# E.net
KiCad netlist of a schematic drawn in EAGLE
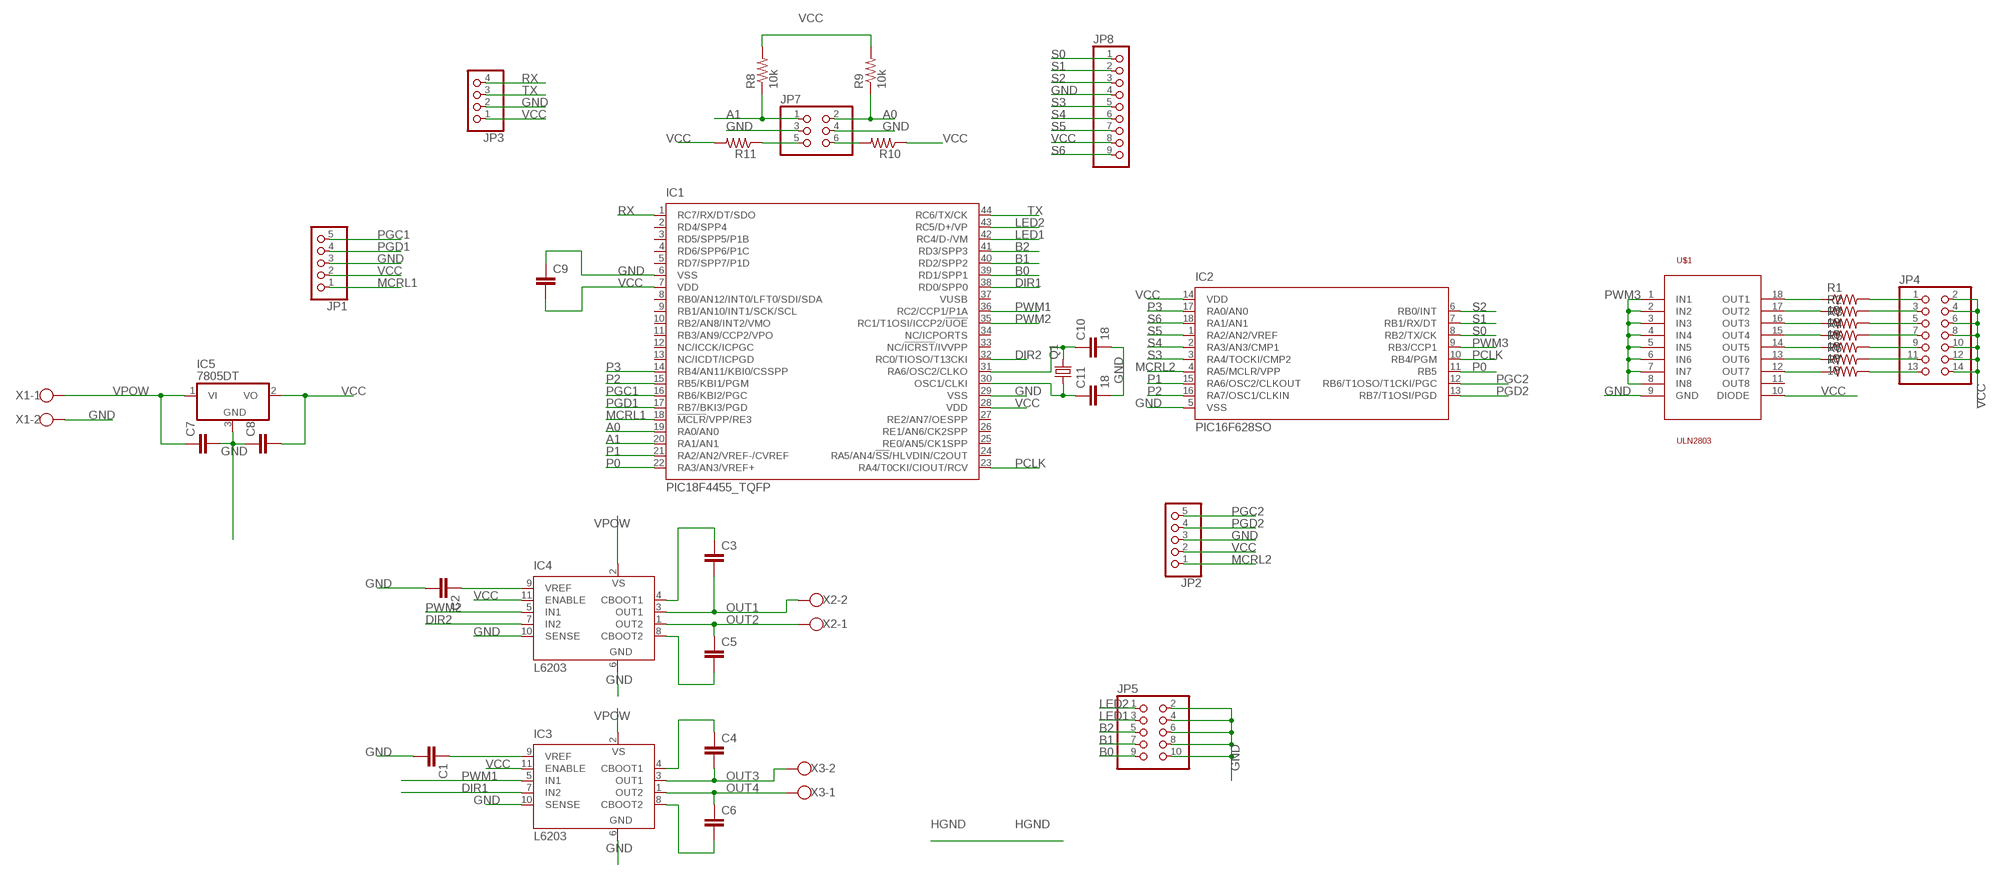
[diagram p0: schematic, sheet 1]

(export (version "E")
  (design (tool "Eeschema 10.0.6"))
  (components
    (comp (ref "C1")
      (value "C2,5-3")
      (footprint "eagle-import:C2.5-3")
      (libsource (lib "eagle-import") (part "C2,5-3"))
    )
    (comp (ref "C2")
      (value "C2,5-3")
      (footprint "eagle-import:C2.5-3")
      (libsource (lib "eagle-import") (part "C2,5-3"))
    )
    (comp (ref "C3")
      (value "C2,5-3")
      (footprint "eagle-import:C2.5-3")
      (libsource (lib "eagle-import") (part "C2,5-3"))
    )
    (comp (ref "C4")
      (value "C2,5-3")
      (footprint "eagle-import:C2.5-3")
      (libsource (lib "eagle-import") (part "C2,5-3"))
    )
    (comp (ref "C5")
      (value "C2,5-3")
      (footprint "eagle-import:C2.5-3")
      (libsource (lib "eagle-import") (part "C2,5-3"))
    )
    (comp (ref "C6")
      (value "C2,5-3")
      (footprint "eagle-import:C2.5-3")
      (libsource (lib "eagle-import") (part "C2,5-3"))
    )
    (comp (ref "C7")
      (value "C2,5-3")
      (footprint "eagle-import:C2.5-3")
      (libsource (lib "eagle-import") (part "C2,5-3"))
    )
    (comp (ref "C8")
      (value "C2,5-3")
      (footprint "eagle-import:C2.5-3")
      (libsource (lib "eagle-import") (part "C2,5-3"))
    )
    (comp (ref "C9")
      (value "C2,5-3")
      (footprint "eagle-import:C2.5-3")
      (libsource (lib "eagle-import") (part "C2,5-3"))
    )
    (comp (ref "C10")
      (value "18")
      (footprint "eagle-import:C2.5-3")
      (libsource (lib "eagle-import") (part "C2,5-3"))
    )
    (comp (ref "C11")
      (value "18")
      (footprint "eagle-import:C2.5-3")
      (libsource (lib "eagle-import") (part "C2,5-3"))
    )
    (comp (ref "IC1")
      (value "PIC18F4455_TQFP")
      (footprint "eagle-import:TQFP44")
      (fields (field (name "MF") "MICROCHIP") (field (name "MPN") "PIC18F4455-I/PT"))
      (libsource (lib "eagle-import") (part "PIC18F4_TQFP455"))
    )
    (comp (ref "IC2")
      (value "PIC16F628SO")
      (footprint "eagle-import:SO-18W")
      (fields (field (name "MF") "MICROCHIP") (field (name "MPN") "PIC16F628-20I/SO"))
      (libsource (lib "eagle-import") (part "PIC16F62SO8"))
    )
    (comp (ref "IC3")
      (value "L6203")
      (footprint "eagle-import:MULTIWATT-11")
      (libsource (lib "eagle-import") (part "L6203"))
    )
    (comp (ref "IC4")
      (value "L6203")
      (footprint "eagle-import:MULTIWATT-11")
      (libsource (lib "eagle-import") (part "L6203"))
    )
    (comp (ref "IC5")
      (value "7805DT")
      (footprint "eagle-import:TO252")
      (libsource (lib "eagle-import") (part "78DT05"))
    )
    (comp (ref "JP1")
      (value "PINHD-1X5")
      (footprint "eagle-import:1X05")
      (libsource (lib "eagle-import") (part "PINHD-1X5"))
    )
    (comp (ref "JP2")
      (value "PINHD-1X5")
      (footprint "eagle-import:1X05")
      (libsource (lib "eagle-import") (part "PINHD-1X5"))
    )
    (comp (ref "JP3")
      (value "PINHD-1X4")
      (footprint "eagle-import:1X04")
      (libsource (lib "eagle-import") (part "PINHD-1X4"))
    )
    (comp (ref "JP4")
      (value "PINHD-2X7")
      (footprint "eagle-import:2X07")
      (libsource (lib "eagle-import") (part "PINHD-2X7"))
    )
    (comp (ref "JP5")
      (value "PINHD-2X5")
      (footprint "eagle-import:2X05")
      (libsource (lib "eagle-import") (part "PINHD-2X5"))
    )
    (comp (ref "JP7")
      (value "PINHD-2X3")
      (footprint "eagle-import:2X03")
      (libsource (lib "eagle-import") (part "PINHD-2X3"))
    )
    (comp (ref "JP8")
      (value "PINHD-1X9")
      (footprint "eagle-import:1X09")
      (libsource (lib "eagle-import") (part "PINHD-1X9"))
    )
    (comp (ref "Q1")
      (value "CRYSTALHC49S")
      (footprint "eagle-import:HC49_S")
      (libsource (lib "eagle-import") (part "CRYSTALHC49S"))
    )
    (comp (ref "R1")
      (value "18")
      (footprint "eagle-import:M1206")
      (libsource (lib "eagle-import") (part "R-US_M1206"))
    )
    (comp (ref "R2")
      (value "18")
      (footprint "eagle-import:M1206")
      (libsource (lib "eagle-import") (part "R-US_M1206"))
    )
    (comp (ref "R3")
      (value "18")
      (footprint "eagle-import:M1206")
      (libsource (lib "eagle-import") (part "R-US_M1206"))
    )
    (comp (ref "R4")
      (value "18")
      (footprint "eagle-import:M1206")
      (libsource (lib "eagle-import") (part "R-US_M1206"))
    )
    (comp (ref "R5")
      (value "18")
      (footprint "eagle-import:M1206")
      (libsource (lib "eagle-import") (part "R-US_M1206"))
    )
    (comp (ref "R6")
      (value "18")
      (footprint "eagle-import:M1206")
      (libsource (lib "eagle-import") (part "R-US_M1206"))
    )
    (comp (ref "R7")
      (value "R-US_M1206")
      (footprint "eagle-import:M1206")
      (libsource (lib "eagle-import") (part "R-US_M1206"))
    )
    (comp (ref "R8")
      (value "10k")
      (footprint "eagle-import:M1206")
      (libsource (lib "eagle-import") (part "R-US_M1206"))
    )
    (comp (ref "R9")
      (value "10k")
      (footprint "eagle-import:M1206")
      (libsource (lib "eagle-import") (part "R-US_M1206"))
    )
    (comp (ref "R10")
      (value "R-US_M1206")
      (footprint "eagle-import:M1206")
      (libsource (lib "eagle-import") (part "R-US_M1206"))
    )
    (comp (ref "R11")
      (value "R-US_M1206")
      (footprint "eagle-import:M1206")
      (libsource (lib "eagle-import") (part "R-US_M1206"))
    )
    (comp (ref "U$1")
      (value "ULN2803")
      (footprint "eagle-import:SO18L")
      (libsource (lib "eagle-import") (part "ULN2803"))
    )
    (comp (ref "X1")
      (value "W237-102")
      (footprint "eagle-import:W237-102")
      (fields (field (name "MPN") "237-102"))
      (libsource (lib "eagle-import") (part "W237-102"))
    )
    (comp (ref "X2")
      (value "W237-102")
      (footprint "eagle-import:W237-102")
      (fields (field (name "MPN") "237-102"))
      (libsource (lib "eagle-import") (part "W237-102"))
    )
    (comp (ref "X3")
      (value "W237-102")
      (footprint "eagle-import:W237-102")
      (fields (field (name "MPN") "237-102"))
      (libsource (lib "eagle-import") (part "W237-102"))
    )
  )
  (nets
    (net (code "1") (name "/A0") (class "Default")
      (node (ref "IC1") (pin "19") (pinfunction "RA0/AN0_19") (pintype "bidirectional"))
      (node (ref "JP7") (pin "2") (pinfunction "2_2") (pintype "passive"))
      (node (ref "R9") (pin "1") (pinfunction "1_1") (pintype "passive"))
    )
    (net (code "2") (name "/A1") (class "Default")
      (node (ref "IC1") (pin "20") (pinfunction "RA1/AN1_20") (pintype "bidirectional"))
      (node (ref "JP7") (pin "1") (pinfunction "1_1") (pintype "passive"))
      (node (ref "R8") (pin "1") (pinfunction "1_1") (pintype "passive"))
    )
    (net (code "3") (name "/B0") (class "Default")
      (node (ref "IC1") (pin "39") (pinfunction "RD1/SPP1_39") (pintype "bidirectional"))
      (node (ref "JP5") (pin "9") (pinfunction "9_9") (pintype "passive"))
    )
    (net (code "4") (name "/B1") (class "Default")
      (node (ref "IC1") (pin "40") (pinfunction "RD2/SPP2_40") (pintype "bidirectional"))
      (node (ref "JP5") (pin "7") (pinfunction "7_7") (pintype "passive"))
    )
    (net (code "5") (name "/B2") (class "Default")
      (node (ref "IC1") (pin "41") (pinfunction "RD3/SPP3_41") (pintype "bidirectional"))
      (node (ref "JP5") (pin "5") (pinfunction "5_5") (pintype "passive"))
    )
    (net (code "6") (name "/DIR1") (class "Default")
      (node (ref "IC1") (pin "38") (pinfunction "RD0/SPP0_38") (pintype "bidirectional"))
      (node (ref "IC3") (pin "7") (pinfunction "IN2_7") (pintype "input"))
    )
    (net (code "7") (name "/DIR2") (class "Default")
      (node (ref "IC1") (pin "32") (pinfunction "RC0/TIOSO/T13CKI_32") (pintype "bidirectional"))
      (node (ref "IC4") (pin "7") (pinfunction "IN2_7") (pintype "input"))
    )
    (net (code "8") (name "/GND") (class "Default")
      (node (ref "C1") (pin "2") (pinfunction "2_2") (pintype "passive"))
      (node (ref "C10") (pin "2") (pinfunction "2_2") (pintype "passive"))
      (node (ref "C11") (pin "2") (pinfunction "2_2") (pintype "passive"))
      (node (ref "C2") (pin "2") (pinfunction "2_2") (pintype "passive"))
      (node (ref "C7") (pin "2") (pinfunction "2_2") (pintype "passive"))
      (node (ref "C8") (pin "1") (pinfunction "1_1") (pintype "passive"))
      (node (ref "C9") (pin "1") (pinfunction "1_1") (pintype "passive"))
      (node (ref "IC1") (pin "29") (pinfunction "VSS_29") (pintype "power_in"))
      (node (ref "IC1") (pin "6") (pinfunction "VSS_6") (pintype "power_in"))
      (node (ref "IC2") (pin "5") (pinfunction "VSS_5") (pintype "power_in"))
      (node (ref "IC3") (pin "10") (pinfunction "SENSE_10") (pintype "input"))
      (node (ref "IC3") (pin "6") (pinfunction "GND_6") (pintype "power_in"))
      (node (ref "IC4") (pin "10") (pinfunction "SENSE_10") (pintype "input"))
      (node (ref "IC4") (pin "6") (pinfunction "GND_6") (pintype "power_in"))
      (node (ref "IC5") (pin "3") (pinfunction "GND_3") (pintype "passive"))
      (node (ref "JP1") (pin "3") (pinfunction "3_3") (pintype "passive"))
      (node (ref "JP2") (pin "3") (pinfunction "3_3") (pintype "passive"))
      (node (ref "JP3") (pin "2") (pinfunction "2_2") (pintype "passive"))
      (node (ref "JP5") (pin "10") (pinfunction "10_10") (pintype "passive"))
      (node (ref "JP5") (pin "2") (pinfunction "2_2") (pintype "passive"))
      (node (ref "JP5") (pin "4") (pinfunction "4_4") (pintype "passive"))
      (node (ref "JP5") (pin "6") (pinfunction "6_6") (pintype "passive"))
      (node (ref "JP5") (pin "8") (pinfunction "8_8") (pintype "passive"))
      (node (ref "JP7") (pin "3") (pinfunction "3_3") (pintype "passive"))
      (node (ref "JP7") (pin "4") (pinfunction "4_4") (pintype "passive"))
      (node (ref "JP8") (pin "4") (pinfunction "4_4") (pintype "passive"))
      (node (ref "U$1") (pin "9") (pinfunction "GND_9") (pintype "power_in"))
      (node (ref "X1") (pin "2") (pinfunction "KL_2") (pintype "passive"))
    )
    (net (code "10") (name "/LED1") (class "Default")
      (node (ref "IC1") (pin "42") (pinfunction "RC4/D-/VM_42") (pintype "bidirectional"))
      (node (ref "JP5") (pin "3") (pinfunction "3_3") (pintype "passive"))
    )
    (net (code "11") (name "/LED2") (class "Default")
      (node (ref "IC1") (pin "43") (pinfunction "RC5/D+/VP_43") (pintype "bidirectional"))
      (node (ref "JP5") (pin "1") (pinfunction "1_1") (pintype "passive"))
    )
    (net (code "12") (name "/MCRL1") (class "Default")
      (node (ref "IC1") (pin "18") (pinfunction "~{MCLR}/VPP/RE3_18") (pintype "input"))
      (node (ref "JP1") (pin "1") (pinfunction "1_1") (pintype "passive"))
    )
    (net (code "13") (name "/MCRL2") (class "Default")
      (node (ref "IC2") (pin "4") (pinfunction "RA5/MCLR/VPP_4") (pintype "bidirectional"))
      (node (ref "JP2") (pin "1") (pinfunction "1_1") (pintype "passive"))
    )
    (net (code "14") (name "/OUT1") (class "Default")
      (node (ref "C3") (pin "2") (pinfunction "2_2") (pintype "passive"))
      (node (ref "IC4") (pin "3") (pinfunction "OUT1_3") (pintype "output"))
      (node (ref "X2") (pin "2") (pinfunction "KL_2") (pintype "passive"))
    )
    (net (code "15") (name "/OUT2") (class "Default")
      (node (ref "C5") (pin "1") (pinfunction "1_1") (pintype "passive"))
      (node (ref "IC4") (pin "1") (pinfunction "OUT2_1") (pintype "output"))
      (node (ref "X2") (pin "1") (pinfunction "KL_1") (pintype "passive"))
    )
    (net (code "16") (name "/OUT3") (class "Default")
      (node (ref "C4") (pin "2") (pinfunction "2_2") (pintype "passive"))
      (node (ref "IC3") (pin "3") (pinfunction "OUT1_3") (pintype "output"))
      (node (ref "X3") (pin "2") (pinfunction "KL_2") (pintype "passive"))
    )
    (net (code "17") (name "/OUT4") (class "Default")
      (node (ref "C6") (pin "1") (pinfunction "1_1") (pintype "passive"))
      (node (ref "IC3") (pin "1") (pinfunction "OUT2_1") (pintype "output"))
      (node (ref "X3") (pin "1") (pinfunction "KL_1") (pintype "passive"))
    )
    (net (code "18") (name "/P0") (class "Default")
      (node (ref "IC1") (pin "22") (pinfunction "RA3/AN3/VREF+_22") (pintype "bidirectional"))
      (node (ref "IC2") (pin "11") (pinfunction "RB5_11") (pintype "bidirectional"))
    )
    (net (code "19") (name "/P1") (class "Default")
      (node (ref "IC1") (pin "21") (pinfunction "RA2/AN2/VREF-/CVREF_21") (pintype "bidirectional"))
      (node (ref "IC2") (pin "15") (pinfunction "RA6/OSC2/CLKOUT_15") (pintype "bidirectional"))
    )
    (net (code "20") (name "/P2") (class "Default")
      (node (ref "IC1") (pin "15") (pinfunction "RB5/KBI1/PGM_15") (pintype "bidirectional"))
      (node (ref "IC2") (pin "16") (pinfunction "RA7/OSC1/CLKIN_16") (pintype "bidirectional"))
    )
    (net (code "21") (name "/P3") (class "Default")
      (node (ref "IC1") (pin "14") (pinfunction "RB4/AN11/KBI0/CSSPP_14") (pintype "bidirectional"))
      (node (ref "IC2") (pin "17") (pinfunction "RA0/AN0_17") (pintype "bidirectional"))
    )
    (net (code "22") (name "/PCLK") (class "Default")
      (node (ref "IC1") (pin "23") (pinfunction "RA4/T0CKI/CIOUT/RCV_23") (pintype "bidirectional"))
      (node (ref "IC2") (pin "10") (pinfunction "RB4/PGM_10") (pintype "bidirectional"))
    )
    (net (code "23") (name "/PGC1") (class "Default")
      (node (ref "IC1") (pin "16") (pinfunction "RB6/KBI2/PGC_16") (pintype "bidirectional"))
      (node (ref "JP1") (pin "5") (pinfunction "5_5") (pintype "passive"))
    )
    (net (code "24") (name "/PGC2") (class "Default")
      (node (ref "IC2") (pin "12") (pinfunction "RB6/T1OSO/T1CKI/PGC_12") (pintype "bidirectional"))
      (node (ref "JP2") (pin "5") (pinfunction "5_5") (pintype "passive"))
    )
    (net (code "25") (name "/PGD1") (class "Default")
      (node (ref "IC1") (pin "17") (pinfunction "RB7/BKI3/PGD_17") (pintype "bidirectional"))
      (node (ref "JP1") (pin "4") (pinfunction "4_4") (pintype "passive"))
    )
    (net (code "26") (name "/PGD2") (class "Default")
      (node (ref "IC2") (pin "13") (pinfunction "RB7/T1OSI/PGD_13") (pintype "bidirectional"))
      (node (ref "JP2") (pin "4") (pinfunction "4_4") (pintype "passive"))
    )
    (net (code "27") (name "/PWM1") (class "Default")
      (node (ref "IC1") (pin "36") (pinfunction "RC2/CCP1/P1A_36") (pintype "bidirectional"))
      (node (ref "IC3") (pin "5") (pinfunction "IN1_5") (pintype "input"))
    )
    (net (code "28") (name "/PWM2") (class "Default")
      (node (ref "IC1") (pin "35") (pinfunction "RC1/T1OSI/ICCP2/~{UOE}_35") (pintype "bidirectional"))
      (node (ref "IC4") (pin "5") (pinfunction "IN1_5") (pintype "input"))
    )
    (net (code "29") (name "/PWM3") (class "Default")
      (node (ref "IC2") (pin "9") (pinfunction "RB3/CCP1_9") (pintype "bidirectional"))
      (node (ref "U$1") (pin "1") (pinfunction "IN1_1") (pintype "input"))
      (node (ref "U$1") (pin "2") (pinfunction "IN2_2") (pintype "input"))
      (node (ref "U$1") (pin "3") (pinfunction "IN3_3") (pintype "input"))
      (node (ref "U$1") (pin "4") (pinfunction "IN4_4") (pintype "input"))
      (node (ref "U$1") (pin "5") (pinfunction "IN5_5") (pintype "input"))
      (node (ref "U$1") (pin "6") (pinfunction "IN6_6") (pintype "input"))
      (node (ref "U$1") (pin "7") (pinfunction "IN7_7") (pintype "input"))
      (node (ref "U$1") (pin "8") (pinfunction "IN8_8") (pintype "input"))
    )
    (net (code "30") (name "/RX") (class "Default")
      (node (ref "IC1") (pin "1") (pinfunction "RC7/RX/DT/SDO_1") (pintype "bidirectional"))
      (node (ref "JP3") (pin "4") (pinfunction "4_4") (pintype "passive"))
    )
    (net (code "31") (name "/S0") (class "Default")
      (node (ref "IC2") (pin "8") (pinfunction "RB2/TX/CK_8") (pintype "bidirectional"))
      (node (ref "JP8") (pin "1") (pinfunction "1_1") (pintype "passive"))
    )
    (net (code "32") (name "/S1") (class "Default")
      (node (ref "IC2") (pin "7") (pinfunction "RB1/RX/DT_7") (pintype "bidirectional"))
      (node (ref "JP8") (pin "2") (pinfunction "2_2") (pintype "passive"))
    )
    (net (code "33") (name "/S2") (class "Default")
      (node (ref "IC2") (pin "6") (pinfunction "RB0/INT_6") (pintype "bidirectional"))
      (node (ref "JP8") (pin "3") (pinfunction "3_3") (pintype "passive"))
    )
    (net (code "34") (name "/S3") (class "Default")
      (node (ref "IC2") (pin "3") (pinfunction "RA4/TOCKI/CMP2_3") (pintype "bidirectional"))
      (node (ref "JP8") (pin "5") (pinfunction "5_5") (pintype "passive"))
    )
    (net (code "35") (name "/S4") (class "Default")
      (node (ref "IC2") (pin "2") (pinfunction "RA3/AN3/CMP1_2") (pintype "bidirectional"))
      (node (ref "JP8") (pin "6") (pinfunction "6_6") (pintype "passive"))
    )
    (net (code "36") (name "/S5") (class "Default")
      (node (ref "IC2") (pin "1") (pinfunction "RA2/AN2/VREF_1") (pintype "bidirectional"))
      (node (ref "JP8") (pin "7") (pinfunction "7_7") (pintype "passive"))
    )
    (net (code "37") (name "/S6") (class "Default")
      (node (ref "IC2") (pin "18") (pinfunction "RA1/AN1_18") (pintype "bidirectional"))
      (node (ref "JP8") (pin "9") (pinfunction "9_9") (pintype "passive"))
    )
    (net (code "38") (name "/TX") (class "Default")
      (node (ref "IC1") (pin "44") (pinfunction "RC6/TX/CK_44") (pintype "bidirectional"))
      (node (ref "JP3") (pin "3") (pinfunction "3_3") (pintype "passive"))
    )
    (net (code "39") (name "/VCC") (class "Default")
      (node (ref "C8") (pin "2") (pinfunction "2_2") (pintype "passive"))
      (node (ref "C9") (pin "2") (pinfunction "2_2") (pintype "passive"))
      (node (ref "IC1") (pin "28") (pinfunction "VDD_28") (pintype "power_in"))
      (node (ref "IC1") (pin "7") (pinfunction "VDD_7") (pintype "power_in"))
      (node (ref "IC2") (pin "14") (pinfunction "VDD_14") (pintype "power_in"))
      (node (ref "IC3") (pin "11") (pinfunction "ENABLE_11") (pintype "input"))
      (node (ref "IC4") (pin "11") (pinfunction "ENABLE_11") (pintype "input"))
      (node (ref "IC5") (pin "2") (pinfunction "VO_2") (pintype "passive"))
      (node (ref "JP1") (pin "2") (pinfunction "2_2") (pintype "passive"))
      (node (ref "JP2") (pin "2") (pinfunction "2_2") (pintype "passive"))
      (node (ref "JP3") (pin "1") (pinfunction "1_1") (pintype "passive"))
      (node (ref "JP4") (pin "10") (pinfunction "10_10") (pintype "passive"))
      (node (ref "JP4") (pin "12") (pinfunction "12_12") (pintype "passive"))
      (node (ref "JP4") (pin "14") (pinfunction "14_14") (pintype "passive"))
      (node (ref "JP4") (pin "2") (pinfunction "2_2") (pintype "passive"))
      (node (ref "JP4") (pin "4") (pinfunction "4_4") (pintype "passive"))
      (node (ref "JP4") (pin "6") (pinfunction "6_6") (pintype "passive"))
      (node (ref "JP4") (pin "8") (pinfunction "8_8") (pintype "passive"))
      (node (ref "JP8") (pin "8") (pinfunction "8_8") (pintype "passive"))
      (node (ref "R10") (pin "1") (pinfunction "1_1") (pintype "passive"))
      (node (ref "R11") (pin "2") (pinfunction "2_2") (pintype "passive"))
      (node (ref "R8") (pin "2") (pinfunction "2_2") (pintype "passive"))
      (node (ref "R9") (pin "2") (pinfunction "2_2") (pintype "passive"))
      (node (ref "U$1") (pin "10") (pinfunction "DIODE_10") (pintype "power_in"))
    )
    (net (code "40") (name "/VPOW") (class "Default")
      (node (ref "C7") (pin "1") (pinfunction "1_1") (pintype "passive"))
      (node (ref "IC3") (pin "2") (pinfunction "VS_2") (pintype "power_in"))
      (node (ref "IC4") (pin "2") (pinfunction "VS_2") (pintype "power_in"))
      (node (ref "IC5") (pin "1") (pinfunction "VI_1") (pintype "input"))
      (node (ref "X1") (pin "1") (pinfunction "KL_1") (pintype "passive"))
    )
    (net (code "41") (name "Net-(IC1-OSC1{slash}CLKI)") (class "Default")
      (node (ref "C11") (pin "1") (pinfunction "1_1") (pintype "passive"))
      (node (ref "IC1") (pin "30") (pinfunction "OSC1/CLKI_30") (pintype "input"))
      (node (ref "Q1") (pin "1") (pinfunction "1_1") (pintype "passive"))
    )
    (net (code "42") (name "Net-(IC1-RA6{slash}OSC2{slash}CLKO)") (class "Default")
      (node (ref "C10") (pin "1") (pinfunction "1_1") (pintype "passive"))
      (node (ref "IC1") (pin "31") (pinfunction "RA6/OSC2/CLKO_31") (pintype "output"))
      (node (ref "Q1") (pin "2") (pinfunction "2_2") (pintype "passive"))
    )
    (net (code "43") (name "Net-(IC3-CBOOT1)") (class "Default")
      (node (ref "C4") (pin "1") (pinfunction "1_1") (pintype "passive"))
      (node (ref "IC3") (pin "4") (pinfunction "CBOOT1_4") (pintype "input"))
    )
    (net (code "44") (name "Net-(IC3-CBOOT2)") (class "Default")
      (node (ref "C6") (pin "2") (pinfunction "2_2") (pintype "passive"))
      (node (ref "IC3") (pin "8") (pinfunction "CBOOT2_8") (pintype "input"))
    )
    (net (code "45") (name "Net-(IC3-VREF)") (class "Default")
      (node (ref "C1") (pin "1") (pinfunction "1_1") (pintype "passive"))
      (node (ref "IC3") (pin "9") (pinfunction "VREF_9") (pintype "input"))
    )
    (net (code "46") (name "Net-(IC4-CBOOT1)") (class "Default")
      (node (ref "C3") (pin "1") (pinfunction "1_1") (pintype "passive"))
      (node (ref "IC4") (pin "4") (pinfunction "CBOOT1_4") (pintype "input"))
    )
    (net (code "47") (name "Net-(IC4-CBOOT2)") (class "Default")
      (node (ref "C5") (pin "2") (pinfunction "2_2") (pintype "passive"))
      (node (ref "IC4") (pin "8") (pinfunction "CBOOT2_8") (pintype "input"))
    )
    (net (code "48") (name "Net-(IC4-VREF)") (class "Default")
      (node (ref "C2") (pin "1") (pinfunction "1_1") (pintype "passive"))
      (node (ref "IC4") (pin "9") (pinfunction "VREF_9") (pintype "input"))
    )
    (net (code "49") (name "Net-(JP4-Pad1)") (class "Default")
      (node (ref "JP4") (pin "1") (pinfunction "1_1") (pintype "passive"))
      (node (ref "R1") (pin "2") (pinfunction "2_2") (pintype "passive"))
    )
    (net (code "50") (name "Net-(JP4-Pad3)") (class "Default")
      (node (ref "JP4") (pin "3") (pinfunction "3_3") (pintype "passive"))
      (node (ref "R2") (pin "2") (pinfunction "2_2") (pintype "passive"))
    )
    (net (code "51") (name "Net-(JP4-Pad5)") (class "Default")
      (node (ref "JP4") (pin "5") (pinfunction "5_5") (pintype "passive"))
      (node (ref "R3") (pin "2") (pinfunction "2_2") (pintype "passive"))
    )
    (net (code "52") (name "Net-(JP4-Pad7)") (class "Default")
      (node (ref "JP4") (pin "7") (pinfunction "7_7") (pintype "passive"))
      (node (ref "R4") (pin "2") (pinfunction "2_2") (pintype "passive"))
    )
    (net (code "53") (name "Net-(JP4-Pad9)") (class "Default")
      (node (ref "JP4") (pin "9") (pinfunction "9_9") (pintype "passive"))
      (node (ref "R5") (pin "2") (pinfunction "2_2") (pintype "passive"))
    )
    (net (code "54") (name "Net-(JP4-Pad11)") (class "Default")
      (node (ref "JP4") (pin "11") (pinfunction "11_11") (pintype "passive"))
      (node (ref "R6") (pin "2") (pinfunction "2_2") (pintype "passive"))
    )
    (net (code "55") (name "Net-(JP4-Pad13)") (class "Default")
      (node (ref "JP4") (pin "13") (pinfunction "13_13") (pintype "passive"))
      (node (ref "R7") (pin "2") (pinfunction "2_2") (pintype "passive"))
    )
    (net (code "56") (name "Net-(JP7-Pad5)") (class "Default")
      (node (ref "JP7") (pin "5") (pinfunction "5_5") (pintype "passive"))
      (node (ref "R11") (pin "1") (pinfunction "1_1") (pintype "passive"))
    )
    (net (code "57") (name "Net-(JP7-Pad6)") (class "Default")
      (node (ref "JP7") (pin "6") (pinfunction "6_6") (pintype "passive"))
      (node (ref "R10") (pin "2") (pinfunction "2_2") (pintype "passive"))
    )
    (net (code "58") (name "Net-(U$1-OUT1)") (class "Default")
      (node (ref "R1") (pin "1") (pinfunction "1_1") (pintype "passive"))
      (node (ref "U$1") (pin "18") (pinfunction "OUT1_18") (pintype "open_collector"))
    )
    (net (code "59") (name "Net-(U$1-OUT2)") (class "Default")
      (node (ref "R2") (pin "1") (pinfunction "1_1") (pintype "passive"))
      (node (ref "U$1") (pin "17") (pinfunction "OUT2_17") (pintype "open_collector"))
    )
    (net (code "60") (name "Net-(U$1-OUT3)") (class "Default")
      (node (ref "R3") (pin "1") (pinfunction "1_1") (pintype "passive"))
      (node (ref "U$1") (pin "16") (pinfunction "OUT3_16") (pintype "open_collector"))
    )
    (net (code "61") (name "Net-(U$1-OUT4)") (class "Default")
      (node (ref "R4") (pin "1") (pinfunction "1_1") (pintype "passive"))
      (node (ref "U$1") (pin "15") (pinfunction "OUT4_15") (pintype "open_collector"))
    )
    (net (code "62") (name "Net-(U$1-OUT5)") (class "Default")
      (node (ref "R5") (pin "1") (pinfunction "1_1") (pintype "passive"))
      (node (ref "U$1") (pin "14") (pinfunction "OUT5_14") (pintype "open_collector"))
    )
    (net (code "63") (name "Net-(U$1-OUT6)") (class "Default")
      (node (ref "R6") (pin "1") (pinfunction "1_1") (pintype "passive"))
      (node (ref "U$1") (pin "13") (pinfunction "OUT6_13") (pintype "open_collector"))
    )
    (net (code "64") (name "Net-(U$1-OUT7)") (class "Default")
      (node (ref "R7") (pin "1") (pinfunction "1_1") (pintype "passive"))
      (node (ref "U$1") (pin "12") (pinfunction "OUT7_12") (pintype "open_collector"))
    )
    (net (code "65") (name "unconnected-(IC1-NC{slash}ICCK{slash}ICPGC-Pad12)") (class "Default")
      (node (ref "IC1") (pin "12") (pinfunction "NC/ICCK/ICPGC_12") (pintype "bidirectional"))
    )
    (net (code "66") (name "unconnected-(IC1-NC{slash}ICDT{slash}ICPGD-Pad13)") (class "Default")
      (node (ref "IC1") (pin "13") (pinfunction "NC/ICDT/ICPGD_13") (pintype "bidirectional"))
    )
    (net (code "67") (name "unconnected-(IC1-NC{slash}ICPORTS-Pad34)") (class "Default")
      (node (ref "IC1") (pin "34") (pinfunction "NC/ICPORTS_34") (pintype "input"))
    )
    (net (code "68") (name "unconnected-(IC1-NC{slash}~{ICRST}{slash}IVVPP-Pad33)") (class "Default")
      (node (ref "IC1") (pin "33") (pinfunction "NC/~{ICRST}/IVVPP_33") (pintype "input"))
    )
    (net (code "69") (name "unconnected-(IC1-RA5{slash}AN4{slash}~{SS}{slash}HLVDIN{slash}C2OUT-Pad24)") (class "Default")
      (node (ref "IC1") (pin "24") (pinfunction "RA5/AN4/~{SS}/HLVDIN/C2OUT_24") (pintype "bidirectional"))
    )
    (net (code "70") (name "unconnected-(IC1-RB0{slash}AN12{slash}INT0{slash}LFT0{slash}SDI{slash}SDA-Pad8)") (class "Default")
      (node (ref "IC1") (pin "8") (pinfunction "RB0/AN12/INT0/LFT0/SDI/SDA_8") (pintype "bidirectional"))
    )
    (net (code "71") (name "unconnected-(IC1-RB1{slash}AN10{slash}INT1{slash}SCK{slash}SCL-Pad9)") (class "Default")
      (node (ref "IC1") (pin "9") (pinfunction "RB1/AN10/INT1/SCK/SCL_9") (pintype "bidirectional"))
    )
    (net (code "72") (name "unconnected-(IC1-RB2{slash}AN8{slash}INT2{slash}VMO-Pad10)") (class "Default")
      (node (ref "IC1") (pin "10") (pinfunction "RB2/AN8/INT2/VMO_10") (pintype "bidirectional"))
    )
    (net (code "73") (name "unconnected-(IC1-RB3{slash}AN9{slash}CCP2{slash}VPO-Pad11)") (class "Default")
      (node (ref "IC1") (pin "11") (pinfunction "RB3/AN9/CCP2/VPO_11") (pintype "bidirectional"))
    )
    (net (code "74") (name "unconnected-(IC1-RD4{slash}SPP4-Pad2)") (class "Default")
      (node (ref "IC1") (pin "2") (pinfunction "RD4/SPP4_2") (pintype "bidirectional"))
    )
    (net (code "75") (name "unconnected-(IC1-RD5{slash}SPP5{slash}P1B-Pad3)") (class "Default")
      (node (ref "IC1") (pin "3") (pinfunction "RD5/SPP5/P1B_3") (pintype "bidirectional"))
    )
    (net (code "76") (name "unconnected-(IC1-RD6{slash}SPP6{slash}P1C-Pad4)") (class "Default")
      (node (ref "IC1") (pin "4") (pinfunction "RD6/SPP6/P1C_4") (pintype "bidirectional"))
    )
    (net (code "77") (name "unconnected-(IC1-RD7{slash}SPP7{slash}P1D-Pad5)") (class "Default")
      (node (ref "IC1") (pin "5") (pinfunction "RD7/SPP7/P1D_5") (pintype "bidirectional"))
    )
    (net (code "78") (name "unconnected-(IC1-RE0{slash}AN5{slash}CK1SPP-Pad25)") (class "Default")
      (node (ref "IC1") (pin "25") (pinfunction "RE0/AN5/CK1SPP_25") (pintype "bidirectional"))
    )
    (net (code "79") (name "unconnected-(IC1-RE1{slash}AN6{slash}CK2SPP-Pad26)") (class "Default")
      (node (ref "IC1") (pin "26") (pinfunction "RE1/AN6/CK2SPP_26") (pintype "bidirectional"))
    )
    (net (code "80") (name "unconnected-(IC1-RE2{slash}AN7{slash}OESPP-Pad27)") (class "Default")
      (node (ref "IC1") (pin "27") (pinfunction "RE2/AN7/OESPP_27") (pintype "bidirectional"))
    )
    (net (code "81") (name "unconnected-(IC1-VUSB-Pad37)") (class "Default")
      (node (ref "IC1") (pin "37") (pinfunction "VUSB_37") (pintype "bidirectional"))
    )
    (net (code "82") (name "unconnected-(U$1-OUT8-Pad11)") (class "Default")
      (node (ref "U$1") (pin "11") (pinfunction "OUT8_11") (pintype "open_collector"))
    )
  )
)
